# DAC_Diver.net
KiCad netlist of a schematic drawn in Altium Designer
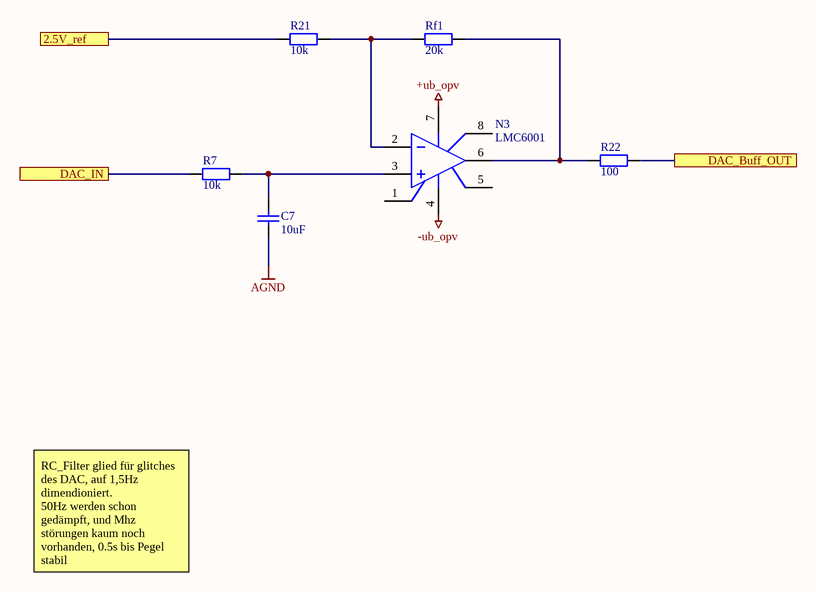
[diagram p0: DAC_Diver.SchDoc]

(export (version "E")
  (design (tool "Eeschema 10.0.6"))
  (components
    (comp (ref "C7")
      (value "10uF")
      (footprint "C1206-KUE")
      (description "Capacitor")
      (fields (field (name "MANUFACTURER") "Kemet") (field (name "PUBLISHER") "Altium Limited"))
      (libsource (lib "ExtrapartsKUE_V01") (part "Capacitor"))
    )
    (comp (ref "N3")
      (value "LMC6001")
      (footprint "DIP8")
      (description "General-Purpose Single Operational Amplifier")
      (fields (field (name "PUBLISHER") "Altium Limited"))
      (libsource (lib "ST Operational Amplifier") (part "UA741AN"))
    )
    (comp (ref "R7")
      (value "10k")
      (footprint "C1206-KUE")
      (description "Resistor SMD")
      (fields (field (name "MANUFACTURER") "AVX") (field (name "PUBLISHER") "Altium Limited"))
      (libsource (lib "ExtrapartsKUE_V01") (part "ResistorSMD"))
    )
    (comp (ref "R21")
      (value "10k")
      (footprint "C1206-KUE")
      (description "Resistor SMD")
      (fields (field (name "MANUFACTURER") "AVX") (field (name "PUBLISHER") "Altium Limited"))
      (libsource (lib "ExtrapartsKUE_V01") (part "ResistorSMD"))
    )
    (comp (ref "R22")
      (value "100")
      (footprint "C1206-KUE")
      (description "Resistor SMD")
      (fields (field (name "MANUFACTURER") "AVX") (field (name "PUBLISHER") "Altium Limited"))
      (libsource (lib "ExtrapartsKUE_V01") (part "ResistorSMD"))
    )
    (comp (ref "Rf1")
      (value "20k")
      (footprint "C1206-KUE")
      (description "Resistor SMD")
      (fields (field (name "MANUFACTURER") "AVX") (field (name "PUBLISHER") "Altium Limited"))
      (libsource (lib "ExtrapartsKUE_V01") (part "ResistorSMD"))
    )
  )
  (nets
    (net (code "1") (name "+ub_opv") (class "Default")
      (node (ref "N3") (pin "7") (pinfunction "V+_7") (pintype "power_in"))
    )
    (net (code "2") (name "-ub_opv") (class "Default")
      (node (ref "N3") (pin "4") (pinfunction "V-_4") (pintype "power_in"))
    )
    (net (code "3") (name "/2.5V_ref") (class "Default")
      (node (ref "R21") (pin "2") (pinfunction "2_2") (pintype "passive"))
    )
    (net (code "4") (name "/DAC_Buff_OUT") (class "Default")
      (node (ref "R22") (pin "1") (pinfunction "1_1") (pintype "passive"))
    )
    (net (code "5") (name "/DAC_IN") (class "Default")
      (node (ref "R7") (pin "2") (pinfunction "2_2") (pintype "passive"))
    )
    (net (code "6") (name "AGND") (class "Default")
      (node (ref "C7") (pin "1") (pinfunction "1_1") (pintype "passive"))
    )
    (net (code "7") (name "Net-(N3-IN+)") (class "Default")
      (node (ref "C7") (pin "2") (pinfunction "2_2") (pintype "passive"))
      (node (ref "N3") (pin "3") (pinfunction "IN+_3") (pintype "passive"))
      (node (ref "R7") (pin "1") (pinfunction "1_1") (pintype "passive"))
    )
    (net (code "8") (name "Net-(N3-IN-)") (class "Default")
      (node (ref "N3") (pin "2") (pinfunction "IN-_2") (pintype "passive"))
      (node (ref "R21") (pin "1") (pinfunction "1_1") (pintype "passive"))
      (node (ref "Rf1") (pin "2") (pinfunction "2_2") (pintype "passive"))
    )
    (net (code "9") (name "Net-(N3-OUT)") (class "Default")
      (node (ref "N3") (pin "6") (pinfunction "OUT_6") (pintype "passive"))
      (node (ref "R22") (pin "2") (pinfunction "2_2") (pintype "passive"))
      (node (ref "Rf1") (pin "1") (pinfunction "1_1") (pintype "passive"))
    )
    (net (code "10") (name "unconnected-(N3-NC-Pad8)") (class "Default")
      (node (ref "N3") (pin "8") (pinfunction "NC_8") (pintype "passive"))
    )
    (net (code "11") (name "unconnected-(N3-OS_NULL-Pad1)") (class "Default")
      (node (ref "N3") (pin "1") (pinfunction "OS_NULL_1") (pintype "passive"))
    )
    (net (code "12") (name "unconnected-(N3-OS_NULL-Pad5)") (class "Default")
      (node (ref "N3") (pin "5") (pinfunction "OS_NULL_5") (pintype "passive"))
    )
  )
)
